# reciever_v1.net
KiCad netlist of a schematic drawn in Altium Designer
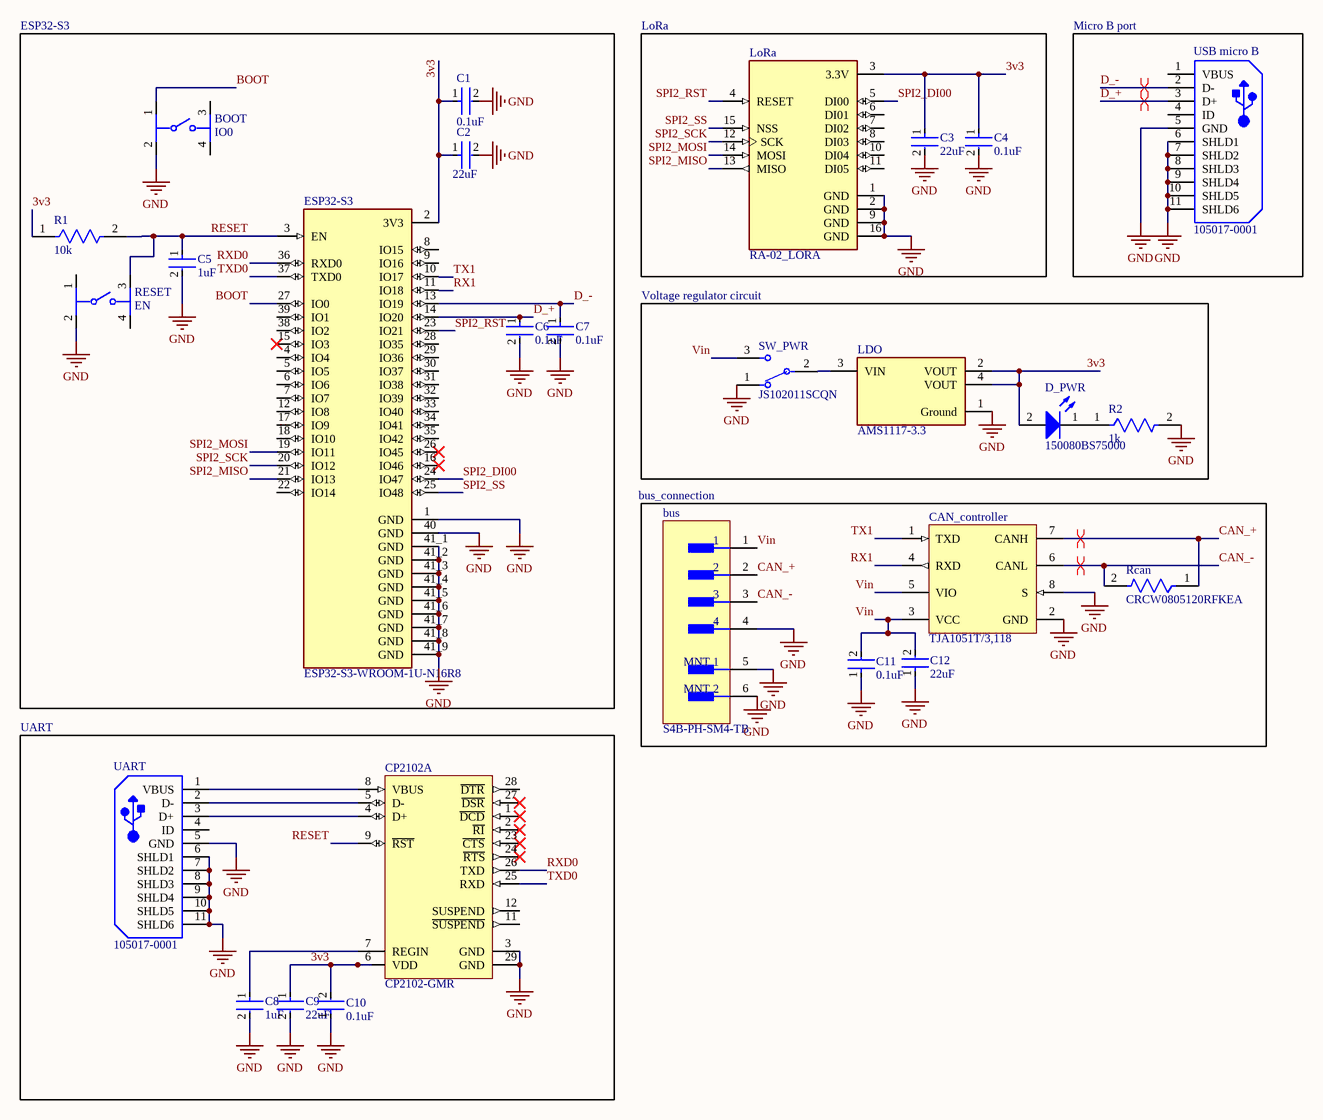
[diagram p0: reciever_v1.SchDoc]

(export (version "E")
  (design (tool "Eeschema 10.0.6"))
  (components
    (comp (ref "BOOT")
      (value "IO0")
      (footprint "FP-8-1437565-1-MFG")
      (description "SWITCH TACTILE SPST-NO 0.02A 15V")
      (libsource (lib "Altium Content Vault") (part "b8895f3f4cefb76e1819d2863dba89b"))
    )
    (comp (ref "bus")
      (value "S4B-PH-SM4-TB")
      (footprint "FP-S4B-PH-SM4-TB-MFG")
      (description "S4B-PH-SM4-TB Header S4B-PH-SM4-TB, 2.00mm, 4-contacts, side entry, SMT, /1000/reel")
      (libsource (lib "Altium Content Vault") (part "S4B-PH-SM4-TB"))
    )
    (comp (ref "C1")
      (value "0.1uF")
      (footprint "FP-0805-L_2_01_0_2-W_1_25-IPC_C")
      (description "General Purpose Ceramic Capacitor, 0805, 100nF, 10%, X7R, 0.15, 50V")
      (fields (field (name "TOLERANCE") "10%") (field (name "VOLTAGE") "50V"))
      (libsource (lib "Altium Content Vault") (part "02cd4be3c70576c341d710602a673aa"))
    )
    (comp (ref "C2")
      (value "22uF")
      (footprint "FP-0805-L_2_01_0_2-W_1_25-IPC_B")
      (description "General Purpose Ceramic Capacitor, 0805, 22uF, 20%, X5R, 15%, 6.3V")
      (fields (field (name "TOLERANCE") "20%") (field (name "VOLTAGE") "6.3V"))
      (libsource (lib "Altium Content Vault") (part "02cd4be3c70576c341d710602a673aa"))
    )
    (comp (ref "C3")
      (value "22uF")
      (footprint "FP-0805-L_2_01_0_2-W_1_25-IPC_B")
      (description "General Purpose Ceramic Capacitor, 0805, 22uF, 20%, X5R, 15%, 6.3V")
      (fields (field (name "TOLERANCE") "20%") (field (name "VOLTAGE") "6.3V"))
      (libsource (lib "Altium Content Vault") (part "02cd4be3c70576c341d710602a673aa"))
    )
    (comp (ref "C4")
      (value "0.1uF")
      (footprint "FP-0805-L_2_01_0_2-W_1_25-IPC_C")
      (description "General Purpose Ceramic Capacitor, 0805, 100nF, 10%, X7R, 0.15, 50V")
      (fields (field (name "TOLERANCE") "10%") (field (name "VOLTAGE") "50V"))
      (libsource (lib "Altium Content Vault") (part "02cd4be3c70576c341d710602a673aa"))
    )
    (comp (ref "C5")
      (value "1uF")
      (footprint "FP-0805-L_2_01_0_2-W_1_25-IPC_B")
      (description "General Purpose Ceramic Capacitor, 0805, 1uF, 10%, X7R, 15%, 25V")
      (fields (field (name "TOLERANCE") "10%") (field (name "VOLTAGE") "25V"))
      (libsource (lib "Altium Content Vault") (part "b4654b650e69147ec39a6b967a45e02"))
    )
    (comp (ref "C6")
      (value "0.1uF")
      (footprint "FP-0805-L_2_01_0_2-W_1_25-IPC_C")
      (description "General Purpose Ceramic Capacitor, 0805, 100nF, 10%, X7R, 0.15, 50V")
      (fields (field (name "TOLERANCE") "10%") (field (name "VOLTAGE") "50V"))
      (libsource (lib "Altium Content Vault") (part "02cd4be3c70576c341d710602a673aa"))
    )
    (comp (ref "C7")
      (value "0.1uF")
      (footprint "FP-0805-L_2_01_0_2-W_1_25-IPC_C")
      (description "General Purpose Ceramic Capacitor, 0805, 100nF, 10%, X7R, 0.15, 50V")
      (fields (field (name "TOLERANCE") "10%") (field (name "VOLTAGE") "50V"))
      (libsource (lib "Altium Content Vault") (part "02cd4be3c70576c341d710602a673aa"))
    )
    (comp (ref "C8")
      (value "1uF")
      (footprint "FP-0805-L_2_01_0_2-W_1_25-IPC_B")
      (description "General Purpose Ceramic Capacitor, 0805, 1uF, 10%, X7R, 15%, 25V")
      (fields (field (name "TOLERANCE") "10%") (field (name "VOLTAGE") "25V"))
      (libsource (lib "Altium Content Vault") (part "b4654b650e69147ec39a6b967a45e02"))
    )
    (comp (ref "C9")
      (value "22uF")
      (footprint "FP-0805-L_2_01_0_2-W_1_25-IPC_B")
      (description "General Purpose Ceramic Capacitor, 0805, 22uF, 20%, X5R, 15%, 6.3V")
      (fields (field (name "TOLERANCE") "20%") (field (name "VOLTAGE") "6.3V"))
      (libsource (lib "Altium Content Vault") (part "02cd4be3c70576c341d710602a673aa"))
    )
    (comp (ref "C10")
      (value "0.1uF")
      (footprint "FP-0805-L_2_01_0_2-W_1_25-IPC_C")
      (description "General Purpose Ceramic Capacitor, 0805, 100nF, 10%, X7R, 0.15, 50V")
      (fields (field (name "TOLERANCE") "10%") (field (name "VOLTAGE") "50V"))
      (libsource (lib "Altium Content Vault") (part "02cd4be3c70576c341d710602a673aa"))
    )
    (comp (ref "C11")
      (value "0.1uF")
      (footprint "FP-0805-L_2_01_0_2-W_1_25-IPC_C")
      (description "General Purpose Ceramic Capacitor, 0805, 100nF, 10%, X7R, 0.15, 50V")
      (fields (field (name "TOLERANCE") "10%") (field (name "VOLTAGE") "50V"))
      (libsource (lib "Altium Content Vault") (part "02cd4be3c70576c341d710602a673aa"))
    )
    (comp (ref "C12")
      (value "22uF")
      (footprint "FP-0805-L_2_01_0_2-W_1_25-IPC_B")
      (description "General Purpose Ceramic Capacitor, 0805, 22uF, 20%, X5R, 15%, 6.3V")
      (fields (field (name "TOLERANCE") "20%") (field (name "VOLTAGE") "6.3V"))
      (libsource (lib "Altium Content Vault") (part "02cd4be3c70576c341d710602a673aa"))
    )
    (comp (ref "CAN_controller")
      (value "TJA1051T/3,118")
      (footprint "NXP-SOIC-8_L")
      (description "High-Speed CAN Transceiver, 3 to 5 V, 8-Pin SOIC (SOT96-1), RoHS, Tape and Reel")
      (fields (field (name "MANUFACTURER") "NXP"))
      (libsource (lib "Altium Content Vault") (part "NXP-TJA1051T_3-SOIC-8"))
    )
    (comp (ref "CP2102")
      (value "CP2102-GMR")
      (footprint "SLAB-QFN-28-3125x3125TP_M")
      (description "Single-Chip USB to URAT Bridge, 3.3 V, -40 to 85 degC, 28-Pin QFN, RoHS, Tape and Reel")
      (fields (field (name "MANUFACTURER") "Silicon Labs"))
      (libsource (lib "Altium Content Vault") (part "SLAB-CP210X-QFN-28-29"))
    )
    (comp (ref "D_PWR")
      (value "150080BS75000")
      (footprint "WL-SMCW_0805_150080xx75000")
      (description "Led, Blue, 470 Nm, 3.2 V, 30 Ma, 145 Mcd Rohs Compliant: Yes")
      (libsource (lib "Altium Content Vault") (part "LED_Blue_2A-1K"))
    )
    (comp (ref "ESP32-S3")
      (value "ESP32-S3-WROOM-1U-N16R8")
      (footprint "XCVR_ESP32-S3-WROOM-1U-N16R8")
      (fields (field (name "MF") "Espressif Systems"))
      (libsource (lib "ESP32-S3-WROOM-1U-N16R8") (part "ESP32-S3-WROOM-1U-N16R8"))
    )
    (comp (ref "LDO")
      (value "AMS1117-3.3")
      (footprint "FP-AMS1117-IPC_C")
      (description "LDO Voltage Regulators 1A, 3.3V")
      (fields
        (field (name "OCTOPART") "https://octopart.com/ams1117-3.3-advanced+monolithic+systems-25899300")
        (field (name "MANUFACTURER") "Advanced Monolithic Systems")
      )
      (libsource (lib "Altium Content Vault") (part "8bdbb5f8e77002000e30dd2845d0354"))
    )
    (comp (ref "LoRa")
      (value "RA-02_LORA")
      (footprint "MODULE_RA-02_LORA")
      (description "Ra-02 LoRa RF M5Stack Platform Evaluation Expansion Board")
      (libsource (lib "RA-02_LORA") (part "RA-02_LORA"))
    )
    (comp (ref "R1")
      (value "10k")
      (footprint "FP-CRCW0805-e3-IPC_A")
      (description "RES Thick Film, 10kΩ, 1%, 0.125W, 100ppm/°C, 0805")
      (fields (field (name "TOLERANCE") "1%"))
      (libsource (lib "Altium Content Vault") (part "1029c3af85768c4190bb7ad29bc67b5"))
    )
    (comp (ref "R2")
      (value "1k")
      (footprint "FP-CRCW0805-e3-MFG")
      (description "RES Thick Film, 1.2kΩ, 1%, 0.125W, 100ppm/°C, 0805")
      (fields (field (name "TOLERANCE") "1%"))
      (libsource (lib "Altium Content Vault") (part "1029c3af85768c4190bb7ad29bc67b5"))
    )
    (comp (ref "Rcan")
      (value "CRCW0805120RFKEA")
      (footprint "FP-CRCW0805-e3-IPC_C")
      (description "RES Thick Film, 120Ω, 1%, 0.125W, 100ppm/°C, 0805")
      (fields (field (name "TOLERANCE") "1%"))
      (libsource (lib "Altium Content Vault") (part "1029c3af85768c4190bb7ad29bc67b5"))
    )
    (comp (ref "RESET")
      (value "EN")
      (footprint "FP-8-1437565-1-MFG")
      (description "SWITCH TACTILE SPST-NO 0.02A 15V")
      (libsource (lib "Altium Content Vault") (part "b8895f3f4cefb76e1819d2863dba89b"))
    )
    (comp (ref "SW_PWR")
      (value "JS102011SCQN")
      (footprint "FP-JS102011SCQN-MFG")
      (description "SWITCH SLIDE SPDT 300MA 6V")
      (libsource (lib "Altium Content Vault") (part "39e195cbbadc85d1df0d7eb6847d379"))
    )
    (comp (ref "UART")
      (value "105017-0001")
      (footprint "USB-MICRO-B_V")
      (fields (field (name "MANUFACTURER") "Molex"))
      (libsource (lib "") (part "USB-5-6SHLD_1"))
    )
    (comp (ref "USB micro B")
      (value "105017-0001")
      (footprint "USB-MICRO-B_V")
      (fields (field (name "MANUFACTURER") "Molex"))
      (libsource (lib "Altium Content Vault") (part "USB-5-6SHLD"))
    )
  )
  (nets
    (net (code "1") (name "/3v3") (class "Default")
      (node (ref "C1") (pin "1") (pinfunction "1_1") (pintype "passive"))
      (node (ref "C10") (pin "2") (pinfunction "2_2") (pintype "passive"))
      (node (ref "C2") (pin "1") (pinfunction "1_1") (pintype "passive"))
      (node (ref "C3") (pin "1") (pinfunction "1_1") (pintype "passive"))
      (node (ref "C4") (pin "1") (pinfunction "1_1") (pintype "passive"))
      (node (ref "C9") (pin "1") (pinfunction "1_1") (pintype "passive"))
      (node (ref "CP2102") (pin "6") (pinfunction "VDD_6") (pintype "power_in"))
      (node (ref "D_PWR") (pin "2") (pinfunction "A_2") (pintype "passive"))
      (node (ref "ESP32-S3") (pin "2") (pinfunction "3V3_2") (pintype "power_in"))
      (node (ref "LDO") (pin "2") (pinfunction "VOUT_2") (pintype "passive"))
      (node (ref "LDO") (pin "4") (pinfunction "VOUT_4") (pintype "passive"))
      (node (ref "LoRa") (pin "3") (pinfunction "3.3V_3") (pintype "power_in"))
      (node (ref "R1") (pin "1") (pinfunction "1_1") (pintype "passive"))
    )
    (net (code "3") (name "/BOOT") (class "Default")
      (node (ref "BOOT") (pin "1") (pinfunction "1_1") (pintype "passive"))
      (node (ref "ESP32-S3") (pin "27") (pinfunction "IO0_27") (pintype "bidirectional"))
    )
    (net (code "4") (name "/CAN_+") (class "Default")
      (node (ref "CAN_controller") (pin "7") (pinfunction "CANH_7") (pintype "passive"))
      (node (ref "Rcan") (pin "1") (pinfunction "1_1") (pintype "passive"))
      (node (ref "bus") (pin "2") (pinfunction "2_2") (pintype "passive"))
    )
    (net (code "5") (name "/CAN_-") (class "Default")
      (node (ref "CAN_controller") (pin "6") (pinfunction "CANL_6") (pintype "passive"))
      (node (ref "Rcan") (pin "2") (pinfunction "2_2") (pintype "passive"))
      (node (ref "bus") (pin "3") (pinfunction "3_3") (pintype "passive"))
    )
    (net (code "6") (name "/D_+") (class "Default")
      (node (ref "C6") (pin "1") (pinfunction "1_1") (pintype "passive"))
      (node (ref "ESP32-S3") (pin "14") (pinfunction "IO20_14") (pintype "bidirectional"))
      (node (ref "USB micro B") (pin "3") (pinfunction "D+_3") (pintype "passive"))
    )
    (net (code "7") (name "/D_-") (class "Default")
      (node (ref "C7") (pin "1") (pinfunction "1_1") (pintype "passive"))
      (node (ref "ESP32-S3") (pin "13") (pinfunction "IO19_13") (pintype "bidirectional"))
      (node (ref "USB micro B") (pin "2") (pinfunction "D-_2") (pintype "passive"))
    )
    (net (code "8") (name "/RESET") (class "Default")
      (node (ref "C5") (pin "1") (pinfunction "1_1") (pintype "passive"))
      (node (ref "CP2102") (pin "9") (pinfunction "~{RST}_9") (pintype "bidirectional"))
      (node (ref "ESP32-S3") (pin "3") (pinfunction "EN_3") (pintype "input"))
      (node (ref "R1") (pin "2") (pinfunction "2_2") (pintype "passive"))
      (node (ref "RESET") (pin "3") (pinfunction "3_3") (pintype "passive"))
    )
    (net (code "9") (name "/RX1") (class "Default")
      (node (ref "CAN_controller") (pin "4") (pinfunction "RXD_4") (pintype "output"))
      (node (ref "ESP32-S3") (pin "11") (pinfunction "IO18_11") (pintype "bidirectional"))
    )
    (net (code "10") (name "/RXD0") (class "Default")
      (node (ref "CP2102") (pin "26") (pinfunction "TXD_26") (pintype "output"))
      (node (ref "ESP32-S3") (pin "36") (pinfunction "RXD0_36") (pintype "bidirectional"))
    )
    (net (code "11") (name "/SPI2_DI00") (class "Default")
      (node (ref "ESP32-S3") (pin "24") (pinfunction "IO47_24") (pintype "bidirectional"))
      (node (ref "LoRa") (pin "5") (pinfunction "DI00_5") (pintype "bidirectional"))
    )
    (net (code "12") (name "/SPI2_MISO") (class "Default")
      (node (ref "ESP32-S3") (pin "21") (pinfunction "IO13_21") (pintype "bidirectional"))
      (node (ref "LoRa") (pin "13") (pinfunction "MISO_13") (pintype "output"))
    )
    (net (code "13") (name "/SPI2_MOSI") (class "Default")
      (node (ref "ESP32-S3") (pin "19") (pinfunction "IO11_19") (pintype "bidirectional"))
      (node (ref "LoRa") (pin "14") (pinfunction "MOSI_14") (pintype "input"))
    )
    (net (code "14") (name "/SPI2_RST") (class "Default")
      (node (ref "ESP32-S3") (pin "23") (pinfunction "IO21_23") (pintype "bidirectional"))
      (node (ref "LoRa") (pin "4") (pinfunction "RESET_4") (pintype "input"))
    )
    (net (code "15") (name "/SPI2_SCK") (class "Default")
      (node (ref "ESP32-S3") (pin "20") (pinfunction "IO12_20") (pintype "bidirectional"))
      (node (ref "LoRa") (pin "12") (pinfunction "SCK_12") (pintype "input"))
    )
    (net (code "16") (name "/SPI2_SS") (class "Default")
      (node (ref "ESP32-S3") (pin "25") (pinfunction "IO48_25") (pintype "bidirectional"))
      (node (ref "LoRa") (pin "15") (pinfunction "NSS_15") (pintype "input"))
    )
    (net (code "17") (name "/TX1") (class "Default")
      (node (ref "CAN_controller") (pin "1") (pinfunction "TXD_1") (pintype "input"))
      (node (ref "ESP32-S3") (pin "10") (pinfunction "IO17_10") (pintype "bidirectional"))
    )
    (net (code "18") (name "/TXD0") (class "Default")
      (node (ref "CP2102") (pin "25") (pinfunction "RXD_25") (pintype "input"))
      (node (ref "ESP32-S3") (pin "37") (pinfunction "TXD0_37") (pintype "bidirectional"))
    )
    (net (code "19") (name "/Vin") (class "Default")
      (node (ref "C11") (pin "2") (pinfunction "2_2") (pintype "passive"))
      (node (ref "C12") (pin "2") (pinfunction "2_2") (pintype "passive"))
      (node (ref "CAN_controller") (pin "3") (pinfunction "VCC_3") (pintype "power_in"))
      (node (ref "CAN_controller") (pin "5") (pinfunction "VIO_5") (pintype "power_in"))
      (node (ref "SW_PWR") (pin "3") (pinfunction "3_3") (pintype "passive"))
      (node (ref "bus") (pin "1") (pinfunction "1_1") (pintype "passive"))
    )
    (net (code "20") (name "GND") (class "Default")
      (node (ref "BOOT") (pin "2") (pinfunction "2_2") (pintype "passive"))
      (node (ref "C1") (pin "2") (pinfunction "2_2") (pintype "passive"))
      (node (ref "C10") (pin "1") (pinfunction "1_1") (pintype "passive"))
      (node (ref "C11") (pin "1") (pinfunction "1_1") (pintype "passive"))
      (node (ref "C12") (pin "1") (pinfunction "1_1") (pintype "passive"))
      (node (ref "C2") (pin "2") (pinfunction "2_2") (pintype "passive"))
      (node (ref "C3") (pin "2") (pinfunction "2_2") (pintype "passive"))
      (node (ref "C4") (pin "2") (pinfunction "2_2") (pintype "passive"))
      (node (ref "C5") (pin "2") (pinfunction "2_2") (pintype "passive"))
      (node (ref "C6") (pin "2") (pinfunction "2_2") (pintype "passive"))
      (node (ref "C7") (pin "2") (pinfunction "2_2") (pintype "passive"))
      (node (ref "C8") (pin "2") (pinfunction "2_2") (pintype "passive"))
      (node (ref "C9") (pin "2") (pinfunction "2_2") (pintype "passive"))
      (node (ref "CAN_controller") (pin "2") (pinfunction "GND_2") (pintype "power_in"))
      (node (ref "CAN_controller") (pin "8") (pinfunction "S_8") (pintype "input"))
      (node (ref "CP2102") (pin "29") (pinfunction "GND_29") (pintype "power_in"))
      (node (ref "CP2102") (pin "3") (pinfunction "GND_3") (pintype "power_in"))
      (node (ref "ESP32-S3") (pin "1") (pinfunction "GND_1") (pintype "power_in"))
      (node (ref "ESP32-S3") (pin "40") (pinfunction "GND_40") (pintype "power_in"))
      (node (ref "ESP32-S3") (pin "41_1") (pinfunction "GND_41_1") (pintype "power_in"))
      (node (ref "ESP32-S3") (pin "41_2") (pinfunction "GND_41_2") (pintype "power_in"))
      (node (ref "ESP32-S3") (pin "41_3") (pinfunction "GND_41_3") (pintype "power_in"))
      (node (ref "ESP32-S3") (pin "41_4") (pinfunction "GND_41_4") (pintype "power_in"))
      (node (ref "ESP32-S3") (pin "41_5") (pinfunction "GND_41_5") (pintype "power_in"))
      (node (ref "ESP32-S3") (pin "41_6") (pinfunction "GND_41_6") (pintype "power_in"))
      (node (ref "ESP32-S3") (pin "41_7") (pinfunction "GND_41_7") (pintype "power_in"))
      (node (ref "ESP32-S3") (pin "41_8") (pinfunction "GND_41_8") (pintype "power_in"))
      (node (ref "ESP32-S3") (pin "41_9") (pinfunction "GND_41_9") (pintype "power_in"))
      (node (ref "LDO") (pin "1") (pinfunction "Ground_1") (pintype "power_in"))
      (node (ref "LoRa") (pin "1") (pinfunction "GND_1") (pintype "power_in"))
      (node (ref "LoRa") (pin "16") (pinfunction "GND_16") (pintype "power_in"))
      (node (ref "LoRa") (pin "2") (pinfunction "GND_2") (pintype "power_in"))
      (node (ref "LoRa") (pin "9") (pinfunction "GND_9") (pintype "power_in"))
      (node (ref "R2") (pin "2") (pinfunction "2_2") (pintype "passive"))
      (node (ref "RESET") (pin "2") (pinfunction "2_2") (pintype "passive"))
      (node (ref "SW_PWR") (pin "1") (pinfunction "1_1") (pintype "passive"))
      (node (ref "UART") (pin "10") (pinfunction "SHLD5_10") (pintype "passive"))
      (node (ref "UART") (pin "11") (pinfunction "SHLD6_11") (pintype "passive"))
      (node (ref "UART") (pin "5") (pinfunction "GND_5") (pintype "passive"))
      (node (ref "UART") (pin "6") (pinfunction "SHLD1_6") (pintype "passive"))
      (node (ref "UART") (pin "7") (pinfunction "SHLD2_7") (pintype "passive"))
      (node (ref "UART") (pin "8") (pinfunction "SHLD3_8") (pintype "passive"))
      (node (ref "UART") (pin "9") (pinfunction "SHLD4_9") (pintype "passive"))
      (node (ref "USB micro B") (pin "10") (pinfunction "SHLD5_10") (pintype "passive"))
      (node (ref "USB micro B") (pin "11") (pinfunction "SHLD6_11") (pintype "passive"))
      (node (ref "USB micro B") (pin "5") (pinfunction "GND_5") (pintype "passive"))
      (node (ref "USB micro B") (pin "6") (pinfunction "SHLD1_6") (pintype "passive"))
      (node (ref "USB micro B") (pin "7") (pinfunction "SHLD2_7") (pintype "passive"))
      (node (ref "USB micro B") (pin "8") (pinfunction "SHLD3_8") (pintype "passive"))
      (node (ref "USB micro B") (pin "9") (pinfunction "SHLD4_9") (pintype "passive"))
      (node (ref "bus") (pin "4") (pinfunction "4_4") (pintype "passive"))
      (node (ref "bus") (pin "5") (pinfunction "MNT_1_5") (pintype "passive"))
      (node (ref "bus") (pin "6") (pinfunction "MNT_2_6") (pintype "passive"))
    )
    (net (code "21") (name "Net-(CP2102A-D+)") (class "Default")
      (node (ref "CP2102") (pin "4") (pinfunction "D+_4") (pintype "bidirectional"))
      (node (ref "UART") (pin "3") (pinfunction "D+_3") (pintype "passive"))
    )
    (net (code "22") (name "Net-(CP2102A-D-)") (class "Default")
      (node (ref "CP2102") (pin "5") (pinfunction "D-_5") (pintype "bidirectional"))
      (node (ref "UART") (pin "2") (pinfunction "D-_2") (pintype "passive"))
    )
    (net (code "23") (name "Net-(CP2102A-REGIN)") (class "Default")
      (node (ref "C8") (pin "1") (pinfunction "1_1") (pintype "passive"))
      (node (ref "CP2102") (pin "7") (pinfunction "REGIN_7") (pintype "power_in"))
    )
    (net (code "24") (name "Net-(CP2102A-VBUS)") (class "Default")
      (node (ref "CP2102") (pin "8") (pinfunction "VBUS_8") (pintype "input"))
      (node (ref "UART") (pin "1") (pinfunction "VBUS_1") (pintype "passive"))
    )
    (net (code "25") (name "Net-(D_PWR-K)") (class "Default")
      (node (ref "D_PWR") (pin "1") (pinfunction "K_1") (pintype "passive"))
      (node (ref "R2") (pin "1") (pinfunction "1_1") (pintype "passive"))
    )
    (net (code "26") (name "Net-(LDO-VIN)") (class "Default")
      (node (ref "LDO") (pin "3") (pinfunction "VIN_3") (pintype "power_in"))
      (node (ref "SW_PWR") (pin "2") (pinfunction "C_2") (pintype "passive"))
    )
    (net (code "27") (name "unconnected-(BOOT-Pad3)") (class "Default")
      (node (ref "BOOT") (pin "3") (pinfunction "3_3") (pintype "passive"))
    )
    (net (code "28") (name "unconnected-(BOOT-Pad4)") (class "Default")
      (node (ref "BOOT") (pin "4") (pinfunction "4_4") (pintype "passive"))
    )
    (net (code "29") (name "unconnected-(CP2102A-SUSPEND-Pad12)") (class "Default")
      (node (ref "CP2102") (pin "12") (pinfunction "SUSPEND_12") (pintype "output"))
    )
    (net (code "30") (name "unconnected-(CP2102A-~{CTS}-Pad23)") (class "Default")
      (node (ref "CP2102") (pin "23") (pinfunction "~{CTS}_23") (pintype "input+no_connect"))
    )
    (net (code "31") (name "unconnected-(CP2102A-~{DCD}-Pad1)") (class "Default")
      (node (ref "CP2102") (pin "1") (pinfunction "~{DCD}_1") (pintype "input+no_connect"))
    )
    (net (code "32") (name "unconnected-(CP2102A-~{DSR}-Pad27)") (class "Default")
      (node (ref "CP2102") (pin "27") (pinfunction "~{DSR}_27") (pintype "input+no_connect"))
    )
    (net (code "33") (name "unconnected-(CP2102A-~{DTR}-Pad28)") (class "Default")
      (node (ref "CP2102") (pin "28") (pinfunction "~{DTR}_28") (pintype "output"))
    )
    (net (code "34") (name "unconnected-(CP2102A-~{RI}-Pad2)") (class "Default")
      (node (ref "CP2102") (pin "2") (pinfunction "~{RI}_2") (pintype "input+no_connect"))
    )
    (net (code "35") (name "unconnected-(CP2102A-~{RTS}-Pad24)") (class "Default")
      (node (ref "CP2102") (pin "24") (pinfunction "~{RTS}_24") (pintype "output+no_connect"))
    )
    (net (code "36") (name "unconnected-(CP2102A-~{SUSPEND}-Pad11)") (class "Default")
      (node (ref "CP2102") (pin "11") (pinfunction "~{SUSPEND}_11") (pintype "output"))
    )
    (net (code "37") (name "unconnected-(ESP32-S3-IO1-Pad39)") (class "Default")
      (node (ref "ESP32-S3") (pin "39") (pinfunction "IO1_39") (pintype "bidirectional"))
    )
    (net (code "38") (name "unconnected-(ESP32-S3-IO2-Pad38)") (class "Default")
      (node (ref "ESP32-S3") (pin "38") (pinfunction "IO2_38") (pintype "bidirectional"))
    )
    (net (code "39") (name "unconnected-(ESP32-S3-IO3-Pad15)") (class "Default")
      (node (ref "ESP32-S3") (pin "15") (pinfunction "IO3_15") (pintype "bidirectional+no_connect"))
    )
    (net (code "40") (name "unconnected-(ESP32-S3-IO4-Pad4)") (class "Default")
      (node (ref "ESP32-S3") (pin "4") (pinfunction "IO4_4") (pintype "bidirectional"))
    )
    (net (code "41") (name "unconnected-(ESP32-S3-IO5-Pad5)") (class "Default")
      (node (ref "ESP32-S3") (pin "5") (pinfunction "IO5_5") (pintype "bidirectional"))
    )
    (net (code "42") (name "unconnected-(ESP32-S3-IO6-Pad6)") (class "Default")
      (node (ref "ESP32-S3") (pin "6") (pinfunction "IO6_6") (pintype "bidirectional"))
    )
    (net (code "43") (name "unconnected-(ESP32-S3-IO7-Pad7)") (class "Default")
      (node (ref "ESP32-S3") (pin "7") (pinfunction "IO7_7") (pintype "bidirectional"))
    )
    (net (code "44") (name "unconnected-(ESP32-S3-IO8-Pad12)") (class "Default")
      (node (ref "ESP32-S3") (pin "12") (pinfunction "IO8_12") (pintype "bidirectional"))
    )
    (net (code "45") (name "unconnected-(ESP32-S3-IO9-Pad17)") (class "Default")
      (node (ref "ESP32-S3") (pin "17") (pinfunction "IO9_17") (pintype "bidirectional"))
    )
    (net (code "46") (name "unconnected-(ESP32-S3-IO10-Pad18)") (class "Default")
      (node (ref "ESP32-S3") (pin "18") (pinfunction "IO10_18") (pintype "bidirectional"))
    )
    (net (code "47") (name "unconnected-(ESP32-S3-IO14-Pad22)") (class "Default")
      (node (ref "ESP32-S3") (pin "22") (pinfunction "IO14_22") (pintype "bidirectional"))
    )
    (net (code "48") (name "unconnected-(ESP32-S3-IO15-Pad8)") (class "Default")
      (node (ref "ESP32-S3") (pin "8") (pinfunction "IO15_8") (pintype "bidirectional"))
    )
    (net (code "49") (name "unconnected-(ESP32-S3-IO16-Pad9)") (class "Default")
      (node (ref "ESP32-S3") (pin "9") (pinfunction "IO16_9") (pintype "bidirectional"))
    )
    (net (code "50") (name "unconnected-(ESP32-S3-IO35-Pad28)") (class "Default")
      (node (ref "ESP32-S3") (pin "28") (pinfunction "IO35_28") (pintype "bidirectional"))
    )
    (net (code "51") (name "unconnected-(ESP32-S3-IO36-Pad29)") (class "Default")
      (node (ref "ESP32-S3") (pin "29") (pinfunction "IO36_29") (pintype "bidirectional"))
    )
    (net (code "52") (name "unconnected-(ESP32-S3-IO37-Pad30)") (class "Default")
      (node (ref "ESP32-S3") (pin "30") (pinfunction "IO37_30") (pintype "bidirectional"))
    )
    (net (code "53") (name "unconnected-(ESP32-S3-IO38-Pad31)") (class "Default")
      (node (ref "ESP32-S3") (pin "31") (pinfunction "IO38_31") (pintype "bidirectional"))
    )
    (net (code "54") (name "unconnected-(ESP32-S3-IO39-Pad32)") (class "Default")
      (node (ref "ESP32-S3") (pin "32") (pinfunction "IO39_32") (pintype "bidirectional"))
    )
    (net (code "55") (name "unconnected-(ESP32-S3-IO40-Pad33)") (class "Default")
      (node (ref "ESP32-S3") (pin "33") (pinfunction "IO40_33") (pintype "bidirectional"))
    )
    (net (code "56") (name "unconnected-(ESP32-S3-IO41-Pad34)") (class "Default")
      (node (ref "ESP32-S3") (pin "34") (pinfunction "IO41_34") (pintype "bidirectional"))
    )
    (net (code "57") (name "unconnected-(ESP32-S3-IO42-Pad35)") (class "Default")
      (node (ref "ESP32-S3") (pin "35") (pinfunction "IO42_35") (pintype "bidirectional"))
    )
    (net (code "58") (name "unconnected-(ESP32-S3-IO45-Pad26)") (class "Default")
      (node (ref "ESP32-S3") (pin "26") (pinfunction "IO45_26") (pintype "bidirectional+no_connect"))
    )
    (net (code "59") (name "unconnected-(ESP32-S3-IO46-Pad16)") (class "Default")
      (node (ref "ESP32-S3") (pin "16") (pinfunction "IO46_16") (pintype "bidirectional+no_connect"))
    )
    (net (code "60") (name "unconnected-(LoRa-DI01-Pad6)") (class "Default")
      (node (ref "LoRa") (pin "6") (pinfunction "DI01_6") (pintype "bidirectional"))
    )
    (net (code "61") (name "unconnected-(LoRa-DI02-Pad7)") (class "Default")
      (node (ref "LoRa") (pin "7") (pinfunction "DI02_7") (pintype "bidirectional"))
    )
    (net (code "62") (name "unconnected-(LoRa-DI03-Pad8)") (class "Default")
      (node (ref "LoRa") (pin "8") (pinfunction "DI03_8") (pintype "bidirectional"))
    )
    (net (code "63") (name "unconnected-(LoRa-DI04-Pad10)") (class "Default")
      (node (ref "LoRa") (pin "10") (pinfunction "DI04_10") (pintype "bidirectional"))
    )
    (net (code "64") (name "unconnected-(LoRa-DI05-Pad11)") (class "Default")
      (node (ref "LoRa") (pin "11") (pinfunction "DI05_11") (pintype "bidirectional"))
    )
    (net (code "65") (name "unconnected-(RESET-Pad1)") (class "Default")
      (node (ref "RESET") (pin "1") (pinfunction "1_1") (pintype "passive"))
    )
    (net (code "66") (name "unconnected-(RESET-Pad4)") (class "Default")
      (node (ref "RESET") (pin "4") (pinfunction "4_4") (pintype "passive"))
    )
    (net (code "67") (name "unconnected-(UART-ID-Pad4)") (class "Default")
      (node (ref "UART") (pin "4") (pinfunction "ID_4") (pintype "passive"))
    )
    (net (code "68") (name "unconnected-(USB micro B-ID-Pad4)") (class "Default")
      (node (ref "USB micro B") (pin "4") (pinfunction "ID_4") (pintype "passive"))
    )
    (net (code "69") (name "unconnected-(USB micro B-VBUS-Pad1)") (class "Default")
      (node (ref "USB micro B") (pin "1") (pinfunction "VBUS_1") (pintype "passive"))
    )
  )
)
